# SCH_ArtNetDMX_2024-09-19.net
KiCad netlist of a schematic drawn in EasyEDA
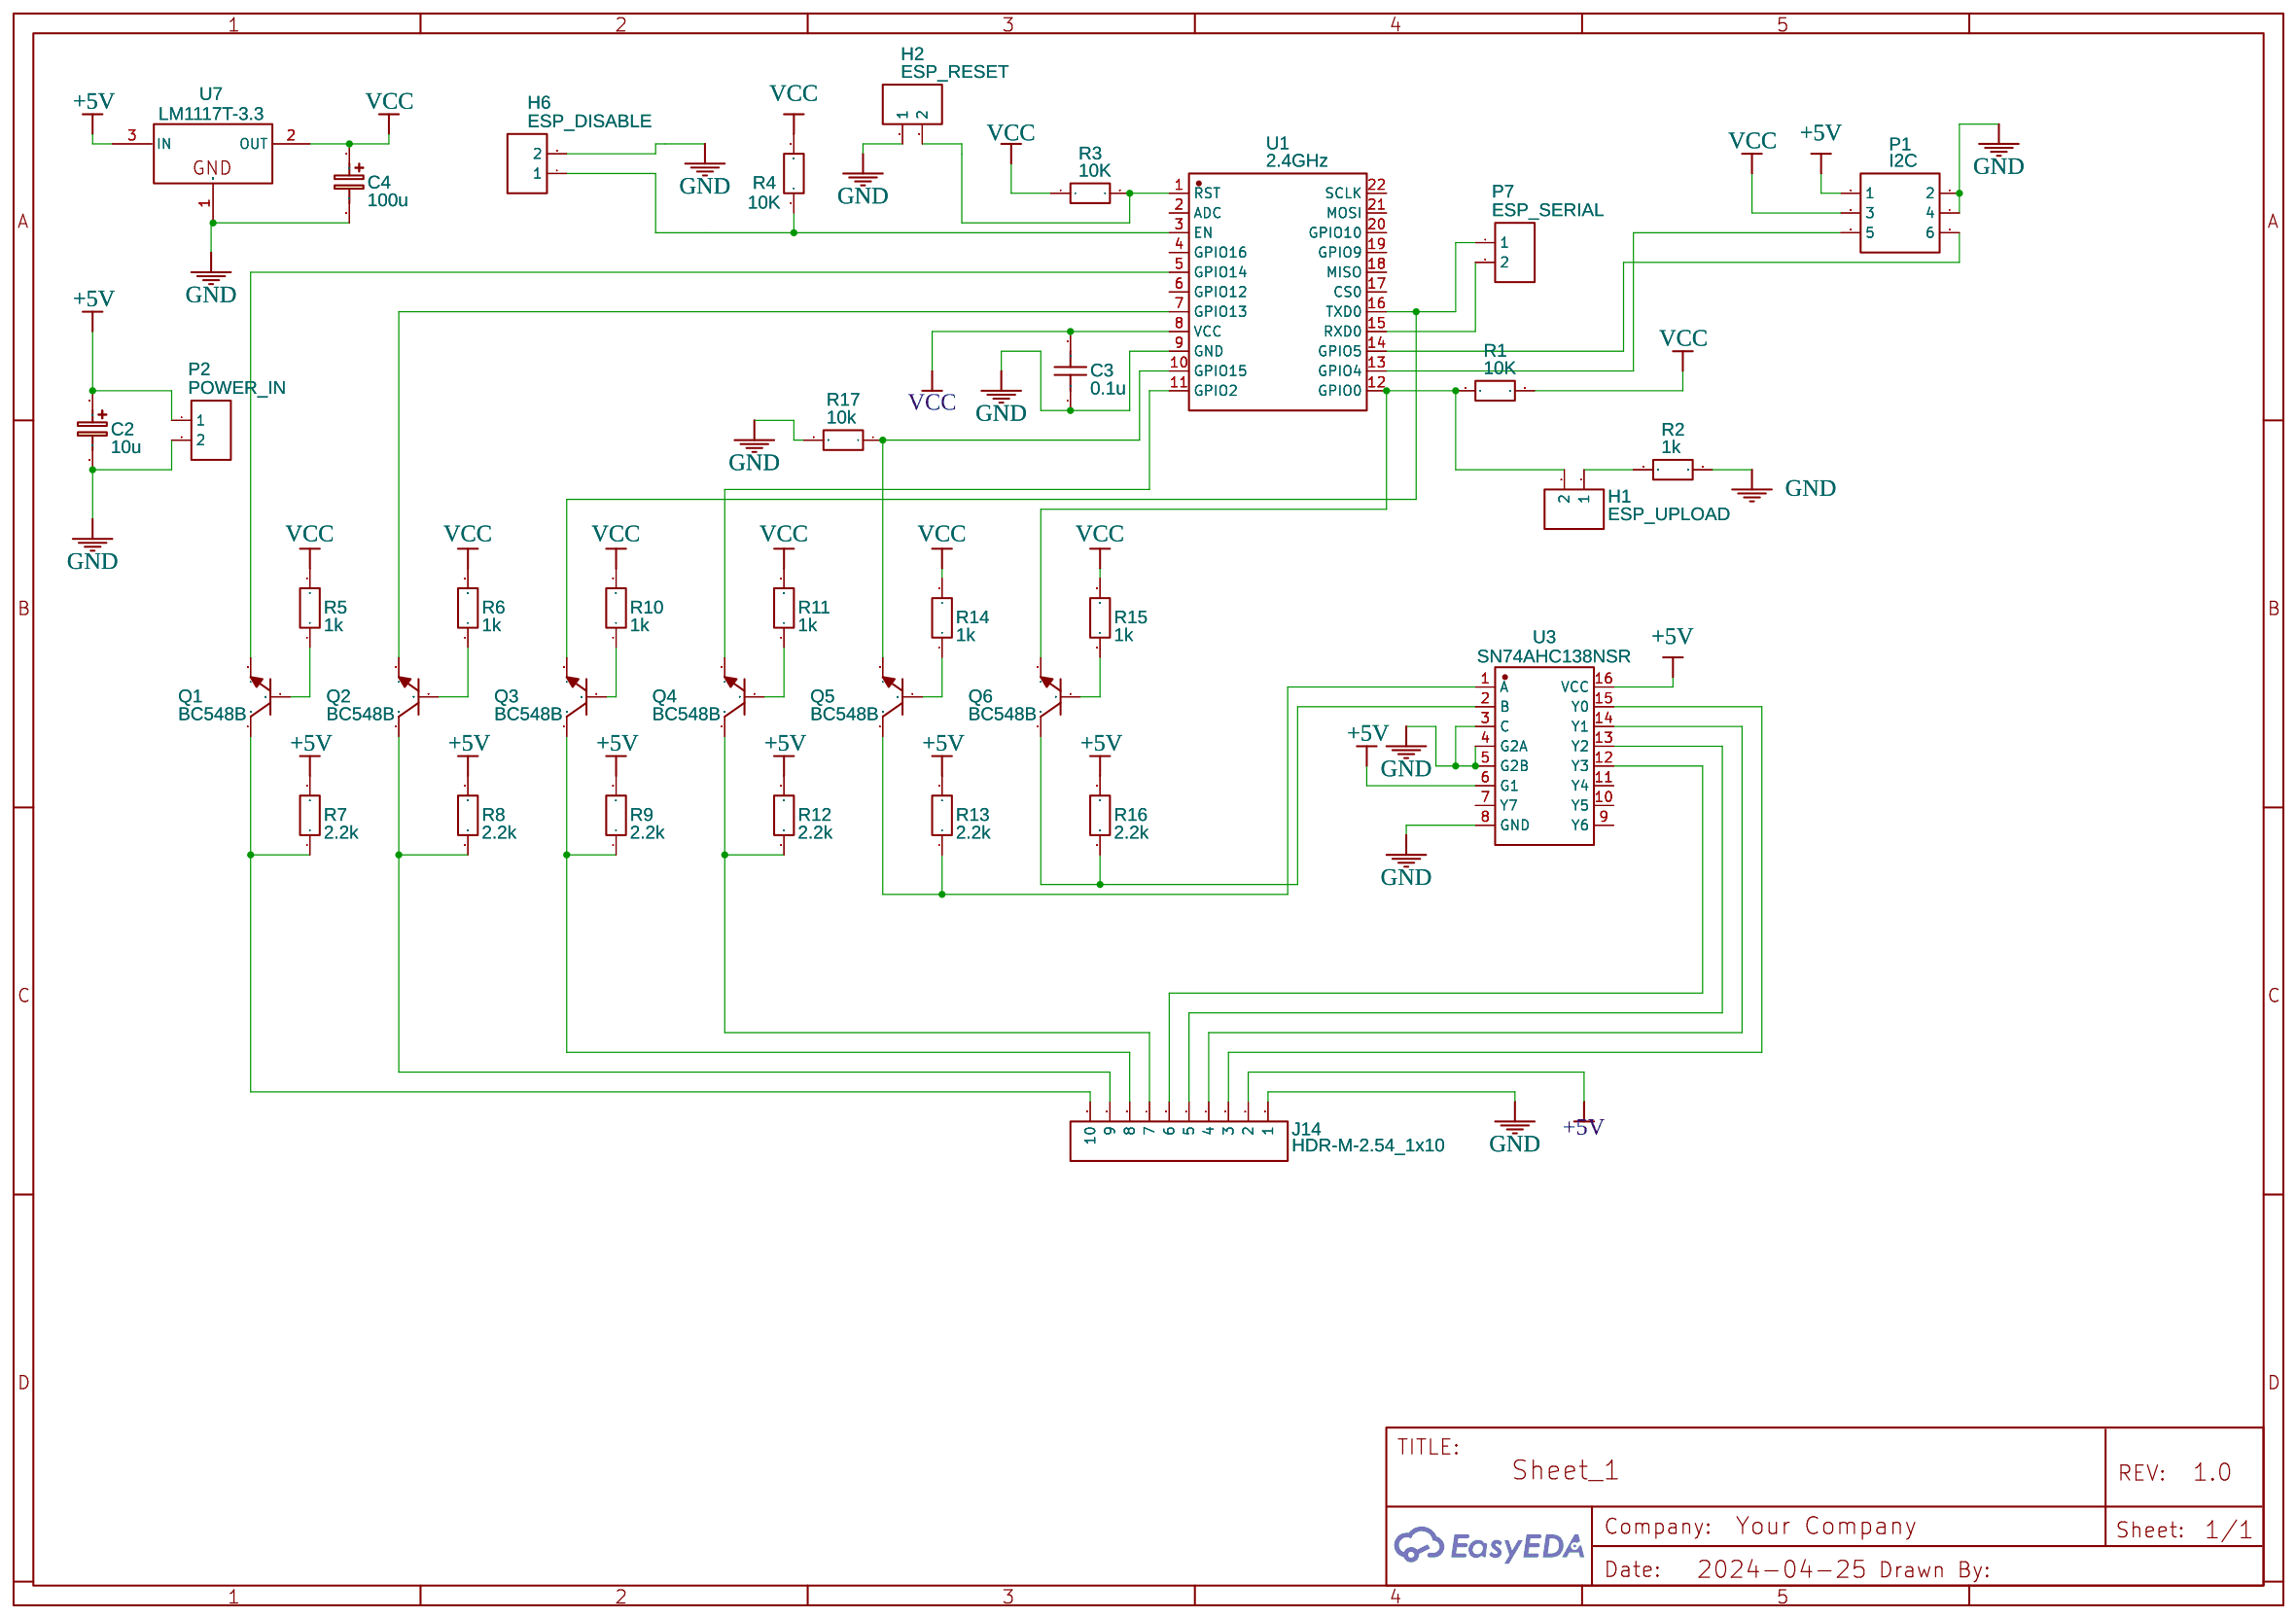
[diagram p0: Sheet_1]
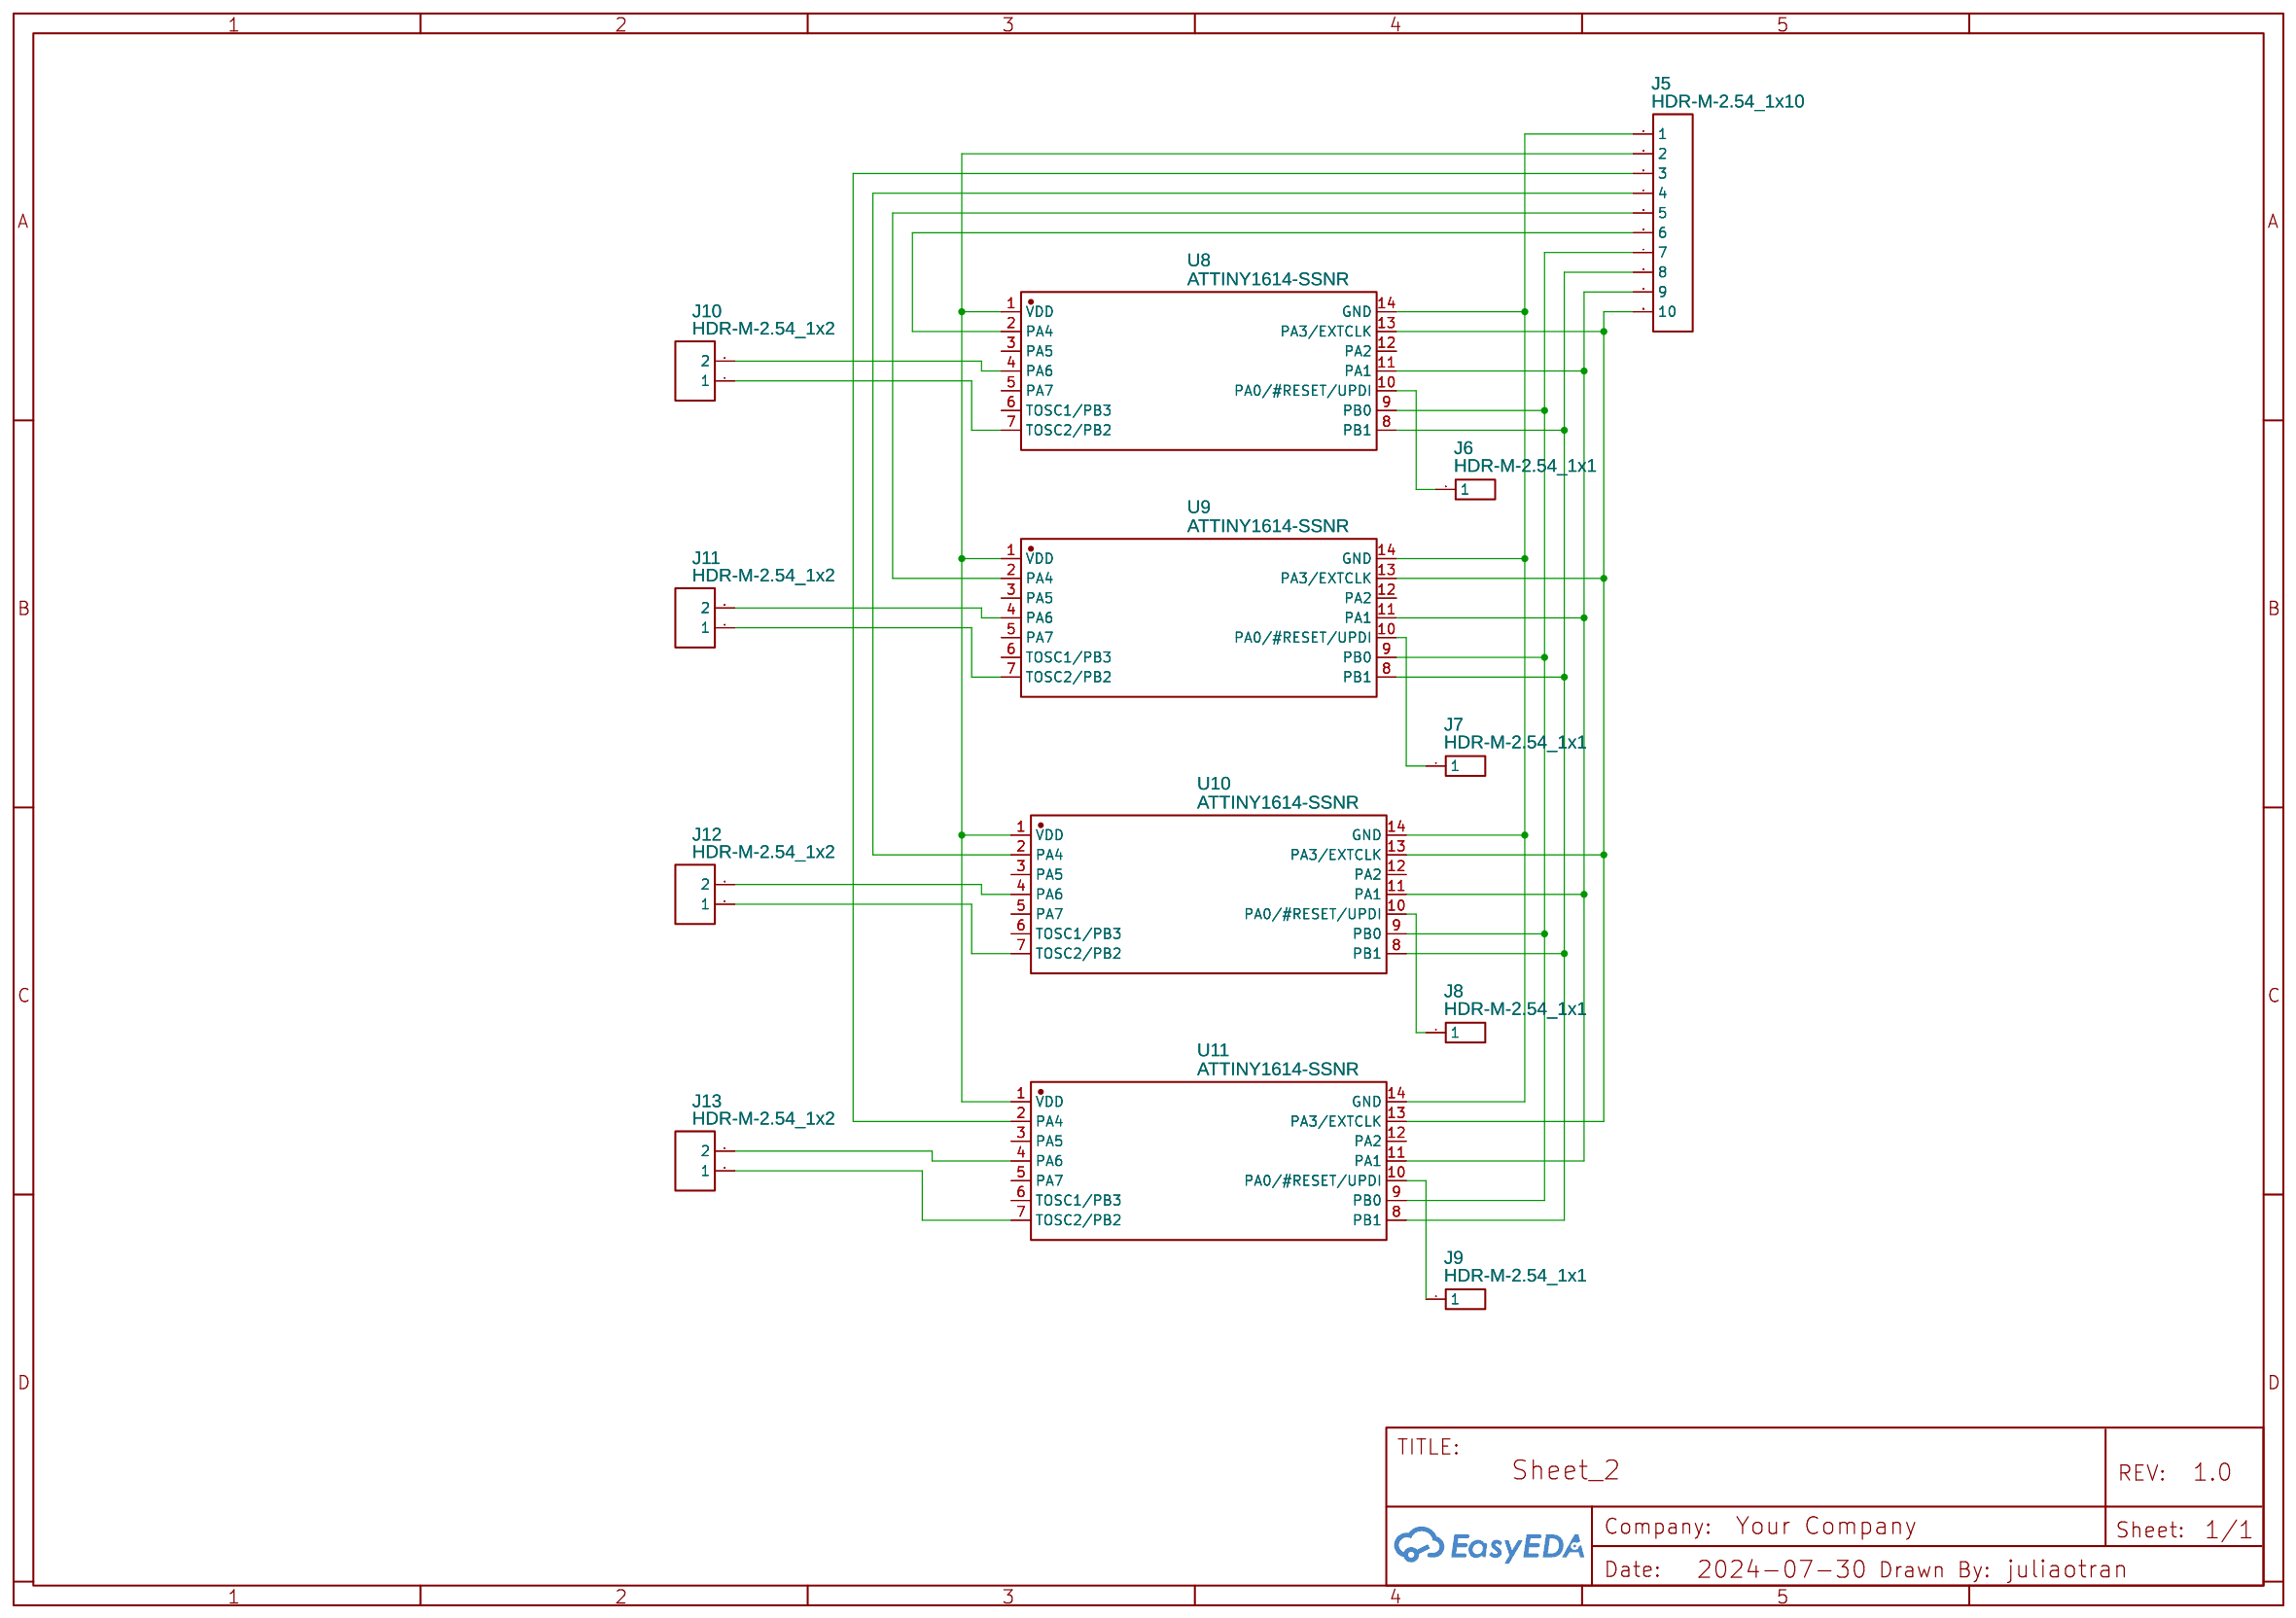
[diagram p1: Sheet_2]
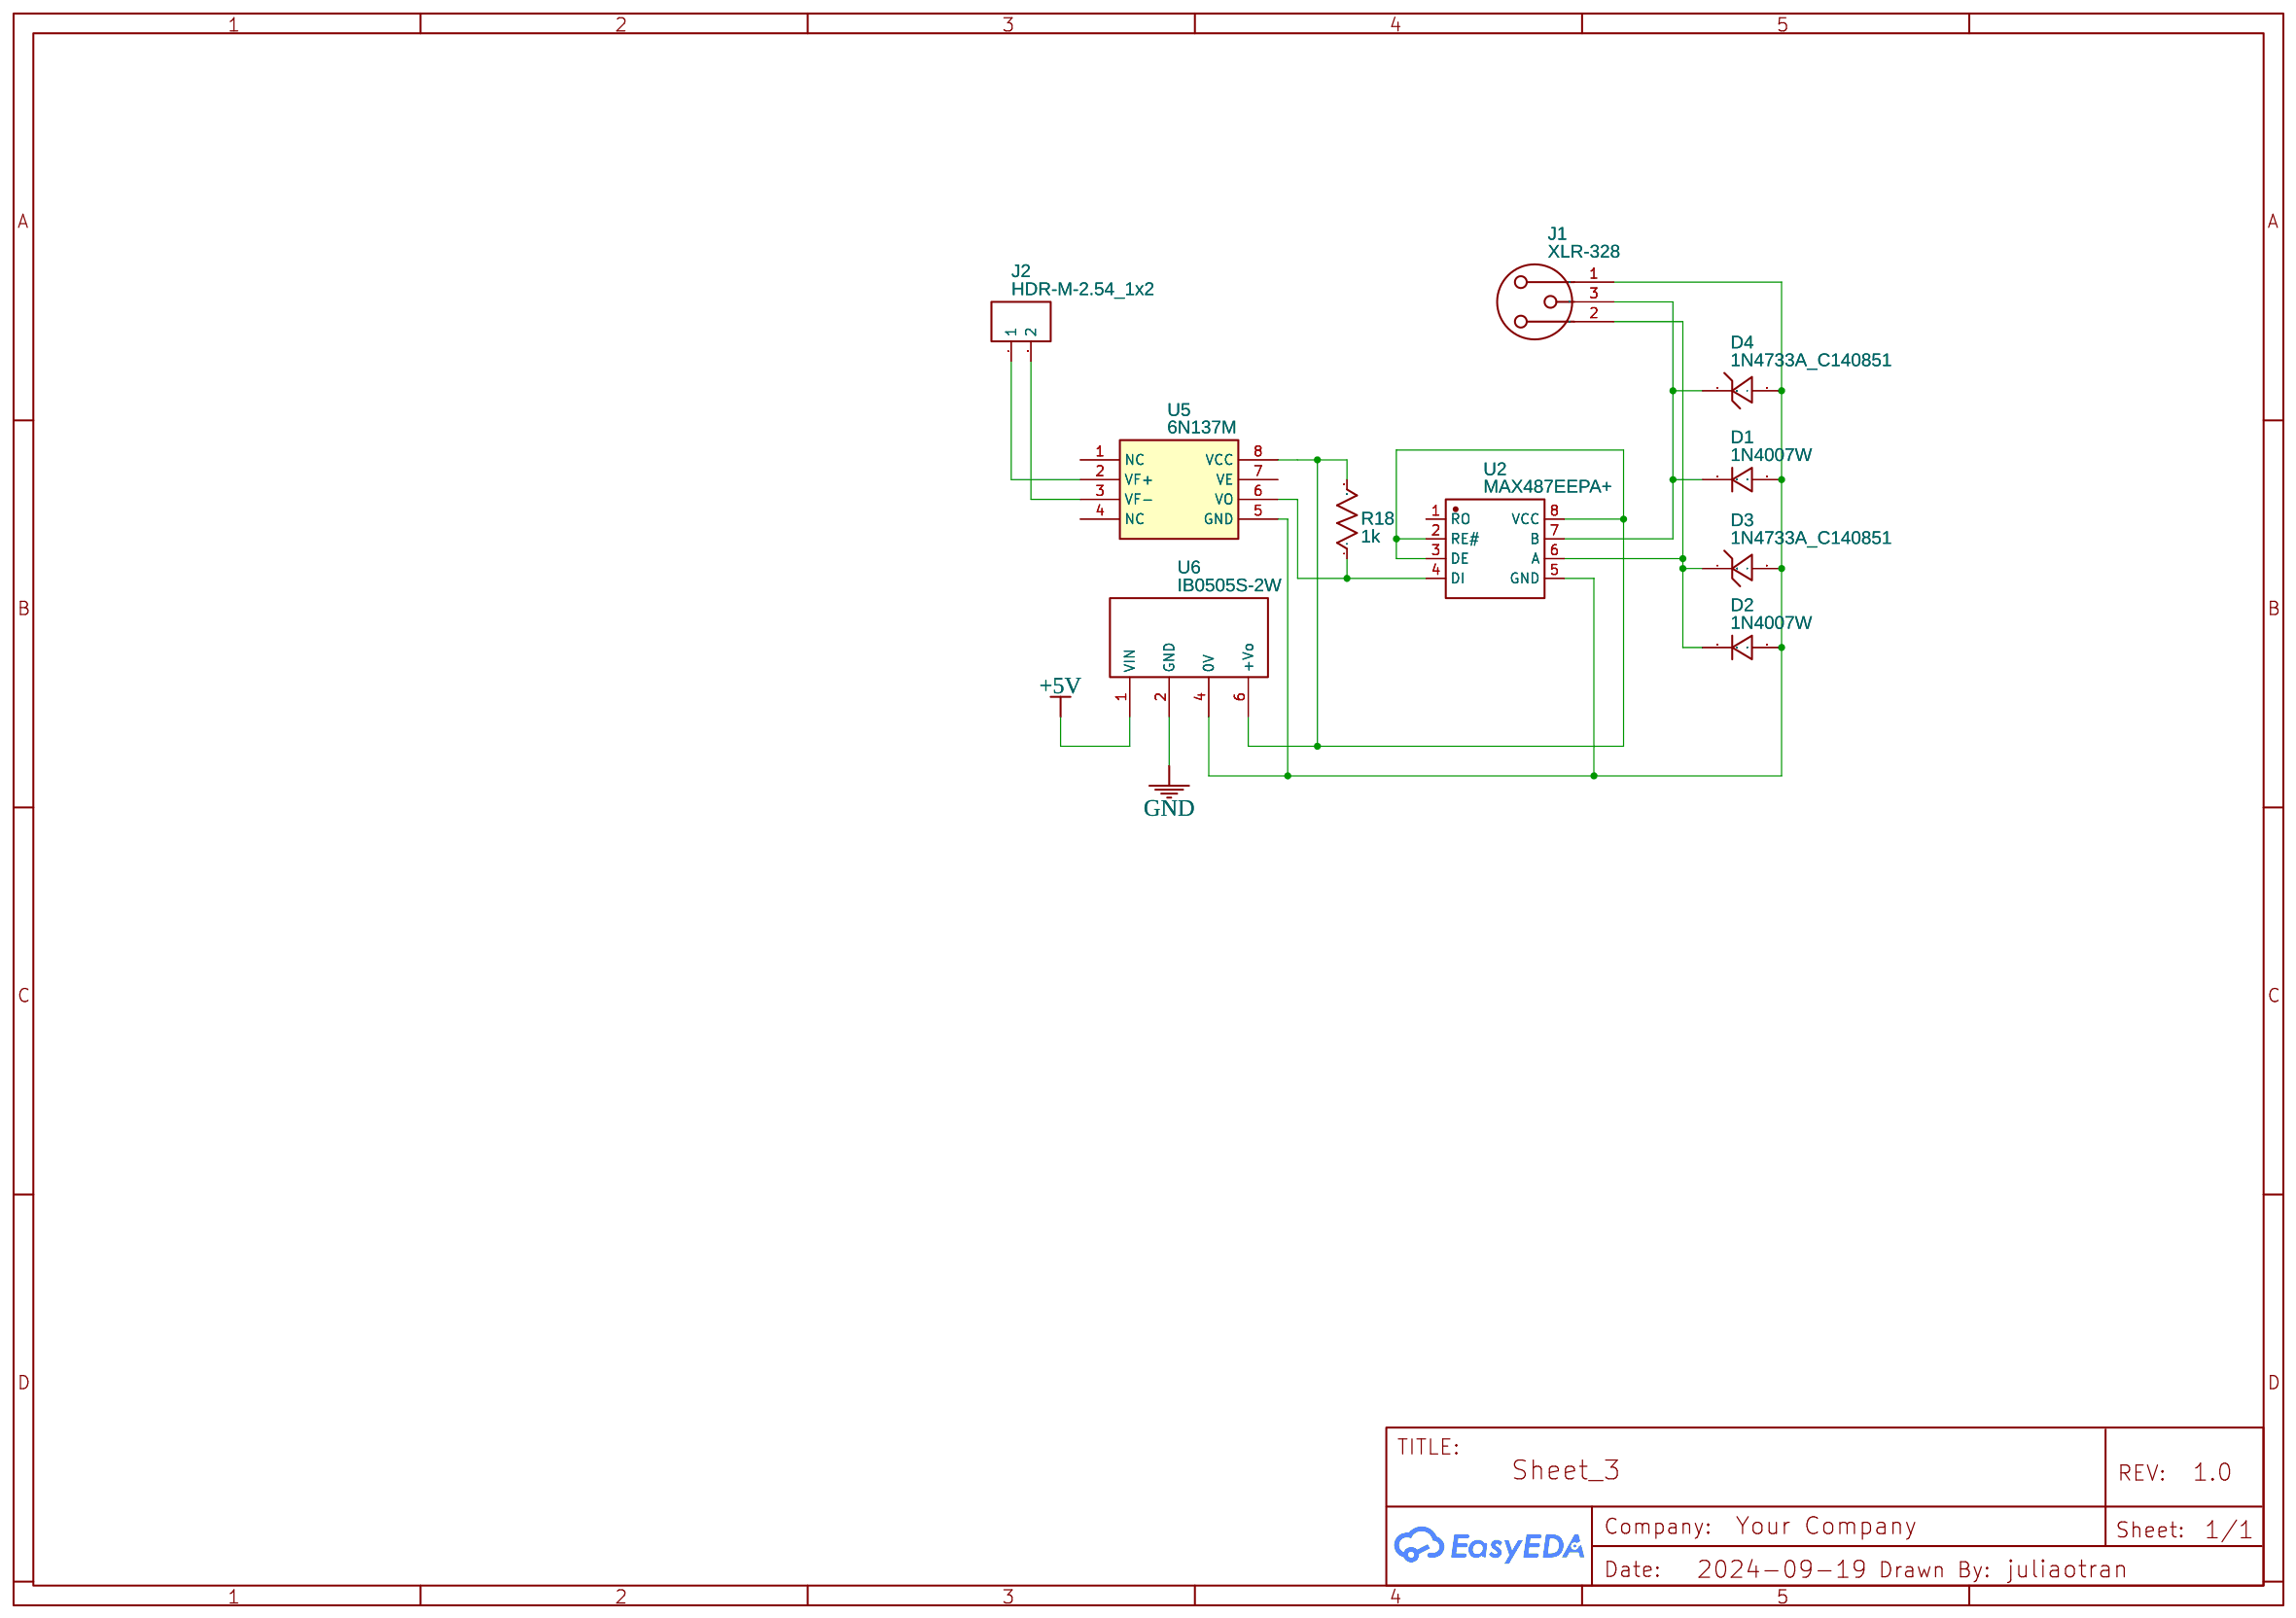
[diagram p2: Sheet_3]

(export (version "E")
  (design (tool "Eeschema 10.0.6"))
  (components
    (comp (ref "C2") (value "10u") (libsource (lib "") (part "CE_SMD_D4.0×H5.5_EU")))
    (comp (ref "C3") (value "0.1u") (libsource (lib "") (part "C_1206_US")))
    (comp (ref "C4") (value "100u") (libsource (lib "") (part "CE_TH_D5.0×F2.0_EU")))
    (comp (ref "H1") (value "ESP_UPLOAD") (libsource (lib "") (part "HDR-F-2.54_1x2")))
    (comp (ref "H2") (value "ESP_RESET") (libsource (lib "") (part "HDR-F-2.54_1x2_1")))
    (comp (ref "H6") (value "ESP_DISABLE") (libsource (lib "") (part "HDR-F-2.54_1x2_2")))
    (comp (ref "J14") (value "HDR-M-2.54_1x10") (libsource (lib "") (part "HDR-M-2.54_1x10")))
    (comp (ref "P1")
      (value "I2C")
      (fields (field (name "Manufacturer Part") "2X3 2.54mm IDC Box") (field (name "Manufacturer") "BOOMELE"))
      (libsource (lib "") (part "HDR-IDC-2.54-2X3P"))
    )
    (comp (ref "P2") (value "POWER_IN") (libsource (lib "") (part "CONN-TH_2P-P5.00")))
    (comp (ref "P7") (value "ESP_SERIAL") (libsource (lib "") (part "CONN-TH_2P-P5.00")))
    (comp (ref "Q1")
      (value "BC548B")
      (fields (field (name "Manufacturer Part") "BC548") (field (name "Manufacturer") "CJ(江苏长电/长晶)"))
      (libsource (lib "") (part "BC548B"))
    )
    (comp (ref "Q2")
      (value "BC548B")
      (fields (field (name "Manufacturer Part") "BC548") (field (name "Manufacturer") "CJ(江苏长电/长晶)"))
      (libsource (lib "") (part "BC548B"))
    )
    (comp (ref "Q3")
      (value "BC548B")
      (fields (field (name "Manufacturer Part") "BC548") (field (name "Manufacturer") "CJ(江苏长电/长晶)"))
      (libsource (lib "") (part "BC548B"))
    )
    (comp (ref "Q4")
      (value "BC548B")
      (fields (field (name "Manufacturer Part") "BC548") (field (name "Manufacturer") "CJ(江苏长电/长晶)"))
      (libsource (lib "") (part "BC548B"))
    )
    (comp (ref "Q5")
      (value "BC548B")
      (fields (field (name "Manufacturer Part") "BC548") (field (name "Manufacturer") "CJ(江苏长电/长晶)"))
      (libsource (lib "") (part "BC548B"))
    )
    (comp (ref "Q6")
      (value "BC548B")
      (fields (field (name "Manufacturer Part") "BC548") (field (name "Manufacturer") "CJ(江苏长电/长晶)"))
      (libsource (lib "") (part "BC548B"))
    )
    (comp (ref "R1") (value "10K") (libsource (lib "") (part "R_0603_EU_1")))
    (comp (ref "R2") (value "1k") (libsource (lib "") (part "R_0603_EU_1")))
    (comp (ref "R3") (value "10K") (libsource (lib "") (part "R_0603_EU_1")))
    (comp (ref "R4") (value "10K") (libsource (lib "") (part "R_0603_EU")))
    (comp (ref "R5") (value "1k") (libsource (lib "") (part "R_0603_EU")))
    (comp (ref "R6") (value "1k") (libsource (lib "") (part "R_0603_EU")))
    (comp (ref "R7") (value "2.2k") (libsource (lib "") (part "R_0603_EU")))
    (comp (ref "R8") (value "2.2k") (libsource (lib "") (part "R_0603_EU")))
    (comp (ref "R9") (value "2.2k") (libsource (lib "") (part "R_0603_EU")))
    (comp (ref "R10") (value "1k") (libsource (lib "") (part "R_0603_EU")))
    (comp (ref "R11") (value "1k") (libsource (lib "") (part "R_0603_EU")))
    (comp (ref "R12") (value "2.2k") (libsource (lib "") (part "R_0603_EU")))
    (comp (ref "R13") (value "2.2k") (libsource (lib "") (part "R_0603_EU")))
    (comp (ref "R14") (value "1k") (libsource (lib "") (part "R_0603_EU")))
    (comp (ref "R15") (value "1k") (libsource (lib "") (part "R_0603_EU")))
    (comp (ref "R16") (value "2.2k") (libsource (lib "") (part "R_0603_EU")))
    (comp (ref "R17") (value "10k") (libsource (lib "") (part "R_0603_EU_2")))
    (comp (ref "U1")
      (value "2.4GHz")
      (fields
        (field (name "Manufacturer Part") "ESP-12F(ESP8266MOD)")
        (field (name "Manufacturer") "Ai-Thinker(安信可)")
      )
      (libsource (lib "") (part "ESP-12F(ESP8266MOD)"))
    )
    (comp (ref "U3")
      (value "SN74AHC138NSR")
      (fields (field (name "Manufacturer") "TI(德州仪器)"))
      (libsource (lib "") (part "SN74AHC138NSR"))
    )
    (comp (ref "U7")
      (value "LM1117T-3.3")
      (fields (field (name "Manufacturer") "HGSEMI(华冠)"))
      (libsource (lib "") (part "LM1117T-3.3"))
    )
    (comp (ref "J5") (value "HDR-M-2.54_1x10") (libsource (lib "") (part "HDR-M-2.54_1x10")))
    (comp (ref "J6") (value "HDR-M-2.54_1x1") (libsource (lib "") (part "HDR-M-2.54_1x1")))
    (comp (ref "J7") (value "HDR-M-2.54_1x1") (libsource (lib "") (part "HDR-M-2.54_1x1")))
    (comp (ref "J8") (value "HDR-M-2.54_1x1") (libsource (lib "") (part "HDR-M-2.54_1x1")))
    (comp (ref "J9") (value "HDR-M-2.54_1x1") (libsource (lib "") (part "HDR-M-2.54_1x1")))
    (comp (ref "J10") (value "HDR-M-2.54_1x2") (libsource (lib "") (part "HDR-M-2.54_1x2")))
    (comp (ref "J11") (value "HDR-M-2.54_1x2") (libsource (lib "") (part "HDR-M-2.54_1x2")))
    (comp (ref "J12") (value "HDR-M-2.54_1x2") (libsource (lib "") (part "HDR-M-2.54_1x2")))
    (comp (ref "J13") (value "HDR-M-2.54_1x2") (libsource (lib "") (part "HDR-M-2.54_1x2")))
    (comp (ref "U8")
      (value "ATTINY1614-SSNR")
      (fields (field (name "Manufacturer") "MICROCHIP(美国微芯)"))
      (libsource (lib "") (part "ATTINY1614-SSNR"))
    )
    (comp (ref "U9")
      (value "ATTINY1614-SSNR")
      (fields (field (name "Manufacturer") "MICROCHIP(美国微芯)"))
      (libsource (lib "") (part "ATTINY1614-SSNR"))
    )
    (comp (ref "U10")
      (value "ATTINY1614-SSNR")
      (fields (field (name "Manufacturer") "MICROCHIP(美国微芯)"))
      (libsource (lib "") (part "ATTINY1614-SSNR"))
    )
    (comp (ref "U11")
      (value "ATTINY1614-SSNR")
      (fields (field (name "Manufacturer") "MICROCHIP(美国微芯)"))
      (libsource (lib "") (part "ATTINY1614-SSNR"))
    )
    (comp (ref "D1")
      (value "1N4007W")
      (fields (field (name "Manufacturer") "BLUE ROCKET"))
      (libsource (lib "") (part "1N4007W"))
    )
    (comp (ref "D2")
      (value "1N4007W")
      (fields (field (name "Manufacturer") "BLUE ROCKET"))
      (libsource (lib "") (part "1N4007W"))
    )
    (comp (ref "D3")
      (value "1N4733A_C140851")
      (fields (field (name "Manufacturer Part") "1N4733A") (field (name "Manufacturer") "onsemi(安森美)"))
      (libsource (lib "") (part "1N4733A_C140851"))
    )
    (comp (ref "D4")
      (value "1N4733A_C140851")
      (fields (field (name "Manufacturer Part") "1N4733A") (field (name "Manufacturer") "onsemi(安森美)"))
      (libsource (lib "") (part "1N4733A_C140851"))
    )
    (comp (ref "J1")
      (value "XLR-328")
      (fields (field (name "Manufacturer") "HOOYA(皓宇电子)"))
      (libsource (lib "") (part "XLR-328"))
    )
    (comp (ref "J2") (value "HDR-M-2.54_1x2") (libsource (lib "") (part "HDR-M-2.54_1x2")))
    (comp (ref "R18") (value "1k") (libsource (lib "") (part "R_0603_US")))
    (comp (ref "U2")
      (value "MAX487EEPA+")
      (fields (field (name "Manufacturer") "ADI(亚德诺)/MAXIM(美信)"))
      (libsource (lib "") (part "MAX487EEPA+"))
    )
    (comp (ref "U5")
      (value "6N137M")
      (fields (field (name "Manufacturer") "onsemi(安森美)"))
      (libsource (lib "") (part "6N137M"))
    )
    (comp (ref "U6")
      (value "IB0505S-2W")
      (fields (field (name "Manufacturer") "MORNSUN(金升阳)"))
      (libsource (lib "") (part "IB0505S-2W"))
    )
  )
  (nets
    (net (code "1") (name "+5V") (class "Default")
      (node (ref "C2") (pin "1") (pinfunction "1_1") (pintype "unspecified"))
      (node (ref "J14") (pin "2") (pinfunction "2_2") (pintype "unspecified"))
      (node (ref "P1") (pin "1") (pinfunction "1_1") (pintype "unspecified"))
      (node (ref "P2") (pin "1") (pinfunction "1_1") (pintype "unspecified"))
      (node (ref "R12") (pin "2") (pinfunction "2_2") (pintype "unspecified"))
      (node (ref "R13") (pin "2") (pinfunction "2_2") (pintype "unspecified"))
      (node (ref "R16") (pin "2") (pinfunction "2_2") (pintype "unspecified"))
      (node (ref "R7") (pin "2") (pinfunction "2_2") (pintype "unspecified"))
      (node (ref "R8") (pin "2") (pinfunction "2_2") (pintype "unspecified"))
      (node (ref "R9") (pin "2") (pinfunction "2_2") (pintype "unspecified"))
      (node (ref "U3") (pin "16") (pinfunction "VCC_16") (pintype "unspecified"))
      (node (ref "U3") (pin "6") (pinfunction "G1_6") (pintype "unspecified"))
      (node (ref "U6") (pin "1") (pinfunction "VIN_1") (pintype "unspecified"))
      (node (ref "U7") (pin "3") (pinfunction "IN_3") (pintype "unspecified"))
    )
    (net (code "2") (name "GND") (class "Default")
      (node (ref "C2") (pin "2") (pinfunction "2_2") (pintype "unspecified"))
      (node (ref "C3") (pin "1") (pinfunction "1_1") (pintype "unspecified"))
      (node (ref "C4") (pin "2") (pinfunction "2_2") (pintype "unspecified"))
      (node (ref "H2") (pin "1") (pinfunction "1_1") (pintype "input"))
      (node (ref "H6") (pin "2") (pinfunction "2_2") (pintype "input"))
      (node (ref "J14") (pin "1") (pinfunction "1_1") (pintype "unspecified"))
      (node (ref "P1") (pin "2") (pinfunction "2_2") (pintype "unspecified"))
      (node (ref "P1") (pin "4") (pinfunction "4_4") (pintype "unspecified"))
      (node (ref "P2") (pin "2") (pinfunction "2_2") (pintype "unspecified"))
      (node (ref "R17") (pin "2") (pinfunction "2_2") (pintype "unspecified"))
      (node (ref "R2") (pin "2") (pinfunction "2_2") (pintype "unspecified"))
      (node (ref "U1") (pin "9") (pinfunction "GND_9") (pintype "unspecified"))
      (node (ref "U3") (pin "3") (pinfunction "C_3") (pintype "unspecified"))
      (node (ref "U3") (pin "4") (pinfunction "G2A_4") (pintype "unspecified"))
      (node (ref "U3") (pin "5") (pinfunction "G2B_5") (pintype "unspecified"))
      (node (ref "U3") (pin "8") (pinfunction "GND_8") (pintype "unspecified"))
      (node (ref "U6") (pin "2") (pinfunction "GND_2") (pintype "unspecified"))
      (node (ref "U7") (pin "1") (pinfunction "GND_1") (pintype "unspecified"))
    )
    (net (code "3") (name "Net-(D3-A)") (class "Default")
      (node (ref "D1") (pin "2") (pinfunction "2_2") (pintype "unspecified"))
      (node (ref "D2") (pin "2") (pinfunction "2_2") (pintype "unspecified"))
      (node (ref "D3") (pin "2") (pinfunction "A_2") (pintype "unspecified"))
      (node (ref "D4") (pin "2") (pinfunction "A_2") (pintype "unspecified"))
      (node (ref "J1") (pin "1") (pinfunction "1_1") (pintype "unspecified"))
      (node (ref "U2") (pin "5") (pinfunction "GND_5") (pintype "unspecified"))
      (node (ref "U5") (pin "5") (pinfunction "GND_5") (pintype "unspecified"))
      (node (ref "U6") (pin "4") (pinfunction "0V_4") (pintype "unspecified"))
    )
    (net (code "4") (name "Net-(D3-C)") (class "Default")
      (node (ref "D2") (pin "1") (pinfunction "1_1") (pintype "unspecified"))
      (node (ref "D3") (pin "1") (pinfunction "C_1") (pintype "unspecified"))
      (node (ref "J1") (pin "2") (pinfunction "2_2") (pintype "unspecified"))
      (node (ref "U2") (pin "6") (pinfunction "A_6") (pintype "unspecified"))
    )
    (net (code "5") (name "Net-(D4-C)") (class "Default")
      (node (ref "D1") (pin "1") (pinfunction "1_1") (pintype "unspecified"))
      (node (ref "D4") (pin "1") (pinfunction "C_1") (pintype "unspecified"))
      (node (ref "J1") (pin "3") (pinfunction "3_3") (pintype "unspecified"))
      (node (ref "U2") (pin "7") (pinfunction "B_7") (pintype "unspecified"))
    )
    (net (code "6") (name "Net-(H1-Pad1)") (class "Default")
      (node (ref "H1") (pin "1") (pinfunction "1_1") (pintype "input"))
      (node (ref "R2") (pin "1") (pinfunction "1_1") (pintype "unspecified"))
    )
    (net (code "7") (name "Net-(Q1-B)") (class "Default")
      (node (ref "Q1") (pin "2") (pinfunction "B_2") (pintype "unspecified"))
      (node (ref "R5") (pin "1") (pinfunction "1_1") (pintype "unspecified"))
    )
    (net (code "8") (name "Net-(Q1-C)") (class "Default")
      (node (ref "J14") (pin "10") (pinfunction "10_10") (pintype "unspecified"))
      (node (ref "Q1") (pin "1") (pinfunction "C_1") (pintype "unspecified"))
      (node (ref "R7") (pin "1") (pinfunction "1_1") (pintype "unspecified"))
    )
    (net (code "9") (name "Net-(Q1-E)") (class "Default")
      (node (ref "Q1") (pin "3") (pinfunction "E_3") (pintype "unspecified"))
      (node (ref "U1") (pin "5") (pinfunction "GPIO14_5") (pintype "unspecified"))
    )
    (net (code "10") (name "Net-(Q2-B)") (class "Default")
      (node (ref "Q2") (pin "2") (pinfunction "B_2") (pintype "unspecified"))
      (node (ref "R6") (pin "1") (pinfunction "1_1") (pintype "unspecified"))
    )
    (net (code "11") (name "Net-(Q2-C)") (class "Default")
      (node (ref "J14") (pin "9") (pinfunction "9_9") (pintype "unspecified"))
      (node (ref "Q2") (pin "1") (pinfunction "C_1") (pintype "unspecified"))
      (node (ref "R8") (pin "1") (pinfunction "1_1") (pintype "unspecified"))
    )
    (net (code "12") (name "Net-(Q2-E)") (class "Default")
      (node (ref "Q2") (pin "3") (pinfunction "E_3") (pintype "unspecified"))
      (node (ref "U1") (pin "7") (pinfunction "GPIO13_7") (pintype "unspecified"))
    )
    (net (code "13") (name "Net-(Q3-B)") (class "Default")
      (node (ref "Q3") (pin "2") (pinfunction "B_2") (pintype "unspecified"))
      (node (ref "R10") (pin "1") (pinfunction "1_1") (pintype "unspecified"))
    )
    (net (code "14") (name "Net-(Q3-C)") (class "Default")
      (node (ref "J14") (pin "8") (pinfunction "8_8") (pintype "unspecified"))
      (node (ref "Q3") (pin "1") (pinfunction "C_1") (pintype "unspecified"))
      (node (ref "R9") (pin "1") (pinfunction "1_1") (pintype "unspecified"))
    )
    (net (code "15") (name "Net-(Q3-E)") (class "Default")
      (node (ref "P7") (pin "1") (pinfunction "1_1") (pintype "unspecified"))
      (node (ref "Q3") (pin "3") (pinfunction "E_3") (pintype "unspecified"))
      (node (ref "U1") (pin "16") (pinfunction "TXD0_16") (pintype "unspecified"))
    )
    (net (code "16") (name "Net-(Q4-B)") (class "Default")
      (node (ref "Q4") (pin "2") (pinfunction "B_2") (pintype "unspecified"))
      (node (ref "R11") (pin "1") (pinfunction "1_1") (pintype "unspecified"))
    )
    (net (code "17") (name "Net-(Q4-C)") (class "Default")
      (node (ref "J14") (pin "7") (pinfunction "7_7") (pintype "unspecified"))
      (node (ref "Q4") (pin "1") (pinfunction "C_1") (pintype "unspecified"))
      (node (ref "R12") (pin "1") (pinfunction "1_1") (pintype "unspecified"))
    )
    (net (code "18") (name "Net-(Q4-E)") (class "Default")
      (node (ref "Q4") (pin "3") (pinfunction "E_3") (pintype "unspecified"))
      (node (ref "U1") (pin "11") (pinfunction "GPIO2_11") (pintype "unspecified"))
    )
    (net (code "19") (name "Net-(Q5-B)") (class "Default")
      (node (ref "Q5") (pin "2") (pinfunction "B_2") (pintype "unspecified"))
      (node (ref "R14") (pin "1") (pinfunction "1_1") (pintype "unspecified"))
    )
    (net (code "20") (name "Net-(Q5-C)") (class "Default")
      (node (ref "Q5") (pin "1") (pinfunction "C_1") (pintype "unspecified"))
      (node (ref "R13") (pin "1") (pinfunction "1_1") (pintype "unspecified"))
      (node (ref "U3") (pin "1") (pinfunction "A_1") (pintype "unspecified"))
    )
    (net (code "21") (name "Net-(Q5-E)") (class "Default")
      (node (ref "Q5") (pin "3") (pinfunction "E_3") (pintype "unspecified"))
      (node (ref "R17") (pin "1") (pinfunction "1_1") (pintype "unspecified"))
      (node (ref "U1") (pin "10") (pinfunction "GPIO15_10") (pintype "unspecified"))
    )
    (net (code "22") (name "Net-(Q6-B)") (class "Default")
      (node (ref "Q6") (pin "2") (pinfunction "B_2") (pintype "unspecified"))
      (node (ref "R15") (pin "1") (pinfunction "1_1") (pintype "unspecified"))
    )
    (net (code "23") (name "Net-(Q6-C)") (class "Default")
      (node (ref "Q6") (pin "1") (pinfunction "C_1") (pintype "unspecified"))
      (node (ref "R16") (pin "1") (pinfunction "1_1") (pintype "unspecified"))
      (node (ref "U3") (pin "2") (pinfunction "B_2") (pintype "unspecified"))
    )
    (net (code "24") (name "Net-(Q6-E)") (class "Default")
      (node (ref "H1") (pin "2") (pinfunction "2_2") (pintype "input"))
      (node (ref "Q6") (pin "3") (pinfunction "E_3") (pintype "unspecified"))
      (node (ref "R1") (pin "1") (pinfunction "1_1") (pintype "unspecified"))
      (node (ref "U1") (pin "12") (pinfunction "GPIO0_12") (pintype "unspecified"))
    )
    (net (code "25") (name "Net-(U1-EN)") (class "Default")
      (node (ref "H6") (pin "1") (pinfunction "1_1") (pintype "input"))
      (node (ref "R4") (pin "1") (pinfunction "1_1") (pintype "unspecified"))
      (node (ref "U1") (pin "3") (pinfunction "EN_3") (pintype "unspecified"))
    )
    (net (code "26") (name "Net-(U1-GPIO4)") (class "Default")
      (node (ref "P1") (pin "5") (pinfunction "5_5") (pintype "unspecified"))
      (node (ref "U1") (pin "13") (pinfunction "GPIO4_13") (pintype "unspecified"))
    )
    (net (code "27") (name "Net-(U1-GPIO5)") (class "Default")
      (node (ref "P1") (pin "6") (pinfunction "6_6") (pintype "unspecified"))
      (node (ref "U1") (pin "14") (pinfunction "GPIO5_14") (pintype "unspecified"))
    )
    (net (code "28") (name "Net-(U1-RST)") (class "Default")
      (node (ref "H2") (pin "2") (pinfunction "2_2") (pintype "input"))
      (node (ref "R3") (pin "2") (pinfunction "2_2") (pintype "unspecified"))
      (node (ref "U1") (pin "1") (pinfunction "RST_1") (pintype "unspecified"))
    )
    (net (code "29") (name "Net-(U1-RXD0)") (class "Default")
      (node (ref "P7") (pin "2") (pinfunction "2_2") (pintype "unspecified"))
      (node (ref "U1") (pin "15") (pinfunction "RXD0_15") (pintype "unspecified"))
    )
    (net (code "30") (name "Net-(U2-DE)") (class "Default")
      (node (ref "R18") (pin "2") (pinfunction "2_2") (pintype "unspecified"))
      (node (ref "U2") (pin "2") (pinfunction "RE#_2") (pintype "unspecified"))
      (node (ref "U2") (pin "3") (pinfunction "DE_3") (pintype "unspecified"))
      (node (ref "U2") (pin "8") (pinfunction "VCC_8") (pintype "unspecified"))
      (node (ref "U5") (pin "8") (pinfunction "VCC_8") (pintype "unspecified"))
      (node (ref "U6") (pin "6") (pinfunction "+Vo_6") (pintype "unspecified"))
    )
    (net (code "31") (name "Net-(U2-DI)") (class "Default")
      (node (ref "R18") (pin "1") (pinfunction "1_1") (pintype "unspecified"))
      (node (ref "U2") (pin "4") (pinfunction "DI_4") (pintype "unspecified"))
      (node (ref "U5") (pin "6") (pinfunction "VO_6") (pintype "unspecified"))
    )
    (net (code "32") (name "Net-(U3-Y0)") (class "Default")
      (node (ref "J14") (pin "3") (pinfunction "3_3") (pintype "unspecified"))
      (node (ref "U3") (pin "15") (pinfunction "Y0_15") (pintype "unspecified"))
    )
    (net (code "33") (name "Net-(U3-Y1)") (class "Default")
      (node (ref "J14") (pin "4") (pinfunction "4_4") (pintype "unspecified"))
      (node (ref "U3") (pin "14") (pinfunction "Y1_14") (pintype "unspecified"))
    )
    (net (code "34") (name "Net-(U3-Y2)") (class "Default")
      (node (ref "J14") (pin "5") (pinfunction "5_5") (pintype "unspecified"))
      (node (ref "U3") (pin "13") (pinfunction "Y2_13") (pintype "unspecified"))
    )
    (net (code "35") (name "Net-(U3-Y3)") (class "Default")
      (node (ref "J14") (pin "6") (pinfunction "6_6") (pintype "unspecified"))
      (node (ref "U3") (pin "12") (pinfunction "Y3_12") (pintype "unspecified"))
    )
    (net (code "36") (name "Net-(U5-VF+)") (class "Default")
      (node (ref "J2") (pin "1") (pinfunction "1_1") (pintype "unspecified"))
      (node (ref "U5") (pin "2") (pinfunction "VF+_2") (pintype "unspecified"))
    )
    (net (code "37") (name "Net-(U5-VF-)") (class "Default")
      (node (ref "J2") (pin "2") (pinfunction "2_2") (pintype "unspecified"))
      (node (ref "U5") (pin "3") (pinfunction "VF-_3") (pintype "unspecified"))
    )
    (net (code "38") (name "Net-(U8-PA0{slash}#RESET{slash}UPDI)") (class "Default")
      (node (ref "J6") (pin "1") (pinfunction "1_1") (pintype "input"))
      (node (ref "U8") (pin "10") (pinfunction "PA0/#RESET/UPDI_10") (pintype "unspecified"))
    )
    (net (code "39") (name "Net-(U8-PA4)") (class "Default")
      (node (ref "J5") (pin "6") (pinfunction "6_6") (pintype "unspecified"))
      (node (ref "U8") (pin "2") (pinfunction "PA4_2") (pintype "unspecified"))
    )
    (net (code "40") (name "Net-(U8-PA6)") (class "Default")
      (node (ref "J10") (pin "2") (pinfunction "2_2") (pintype "unspecified"))
      (node (ref "U8") (pin "4") (pinfunction "PA6_4") (pintype "unspecified"))
    )
    (net (code "41") (name "Net-(U8-TOSC2{slash}PB2)") (class "Default")
      (node (ref "J10") (pin "1") (pinfunction "1_1") (pintype "unspecified"))
      (node (ref "U8") (pin "7") (pinfunction "TOSC2/PB2_7") (pintype "unspecified"))
    )
    (net (code "42") (name "Net-(U9-PA0{slash}#RESET{slash}UPDI)") (class "Default")
      (node (ref "J7") (pin "1") (pinfunction "1_1") (pintype "input"))
      (node (ref "U9") (pin "10") (pinfunction "PA0/#RESET/UPDI_10") (pintype "unspecified"))
    )
    (net (code "43") (name "Net-(U9-PA4)") (class "Default")
      (node (ref "J5") (pin "5") (pinfunction "5_5") (pintype "unspecified"))
      (node (ref "U9") (pin "2") (pinfunction "PA4_2") (pintype "unspecified"))
    )
    (net (code "44") (name "Net-(U9-PA6)") (class "Default")
      (node (ref "J11") (pin "2") (pinfunction "2_2") (pintype "unspecified"))
      (node (ref "U9") (pin "4") (pinfunction "PA6_4") (pintype "unspecified"))
    )
    (net (code "45") (name "Net-(U9-TOSC2{slash}PB2)") (class "Default")
      (node (ref "J11") (pin "1") (pinfunction "1_1") (pintype "unspecified"))
      (node (ref "U9") (pin "7") (pinfunction "TOSC2/PB2_7") (pintype "unspecified"))
    )
    (net (code "46") (name "Net-(U10-GND)") (class "Default")
      (node (ref "J5") (pin "1") (pinfunction "1_1") (pintype "unspecified"))
      (node (ref "U10") (pin "14") (pinfunction "GND_14") (pintype "unspecified"))
      (node (ref "U11") (pin "14") (pinfunction "GND_14") (pintype "unspecified"))
      (node (ref "U8") (pin "14") (pinfunction "GND_14") (pintype "unspecified"))
      (node (ref "U9") (pin "14") (pinfunction "GND_14") (pintype "unspecified"))
    )
    (net (code "47") (name "Net-(U10-PA0{slash}#RESET{slash}UPDI)") (class "Default")
      (node (ref "J8") (pin "1") (pinfunction "1_1") (pintype "input"))
      (node (ref "U10") (pin "10") (pinfunction "PA0/#RESET/UPDI_10") (pintype "unspecified"))
    )
    (net (code "48") (name "Net-(U10-PA1)") (class "Default")
      (node (ref "J5") (pin "9") (pinfunction "9_9") (pintype "unspecified"))
      (node (ref "U10") (pin "11") (pinfunction "PA1_11") (pintype "unspecified"))
      (node (ref "U11") (pin "11") (pinfunction "PA1_11") (pintype "unspecified"))
      (node (ref "U8") (pin "11") (pinfunction "PA1_11") (pintype "unspecified"))
      (node (ref "U9") (pin "11") (pinfunction "PA1_11") (pintype "unspecified"))
    )
    (net (code "49") (name "Net-(U10-PA3{slash}EXTCLK)") (class "Default")
      (node (ref "J5") (pin "10") (pinfunction "10_10") (pintype "unspecified"))
      (node (ref "U10") (pin "13") (pinfunction "PA3/EXTCLK_13") (pintype "unspecified"))
      (node (ref "U11") (pin "13") (pinfunction "PA3/EXTCLK_13") (pintype "unspecified"))
      (node (ref "U8") (pin "13") (pinfunction "PA3/EXTCLK_13") (pintype "unspecified"))
      (node (ref "U9") (pin "13") (pinfunction "PA3/EXTCLK_13") (pintype "unspecified"))
    )
    (net (code "50") (name "Net-(U10-PA4)") (class "Default")
      (node (ref "J5") (pin "4") (pinfunction "4_4") (pintype "unspecified"))
      (node (ref "U10") (pin "2") (pinfunction "PA4_2") (pintype "unspecified"))
    )
    (net (code "51") (name "Net-(U10-PA6)") (class "Default")
      (node (ref "J12") (pin "2") (pinfunction "2_2") (pintype "unspecified"))
      (node (ref "U10") (pin "4") (pinfunction "PA6_4") (pintype "unspecified"))
    )
    (net (code "52") (name "Net-(U10-PB0)") (class "Default")
      (node (ref "J5") (pin "7") (pinfunction "7_7") (pintype "unspecified"))
      (node (ref "U10") (pin "9") (pinfunction "PB0_9") (pintype "unspecified"))
      (node (ref "U11") (pin "9") (pinfunction "PB0_9") (pintype "unspecified"))
      (node (ref "U8") (pin "9") (pinfunction "PB0_9") (pintype "unspecified"))
      (node (ref "U9") (pin "9") (pinfunction "PB0_9") (pintype "unspecified"))
    )
    (net (code "53") (name "Net-(U10-PB1)") (class "Default")
      (node (ref "J5") (pin "8") (pinfunction "8_8") (pintype "unspecified"))
      (node (ref "U10") (pin "8") (pinfunction "PB1_8") (pintype "unspecified"))
      (node (ref "U11") (pin "8") (pinfunction "PB1_8") (pintype "unspecified"))
      (node (ref "U8") (pin "8") (pinfunction "PB1_8") (pintype "unspecified"))
      (node (ref "U9") (pin "8") (pinfunction "PB1_8") (pintype "unspecified"))
    )
    (net (code "54") (name "Net-(U10-TOSC2{slash}PB2)") (class "Default")
      (node (ref "J12") (pin "1") (pinfunction "1_1") (pintype "unspecified"))
      (node (ref "U10") (pin "7") (pinfunction "TOSC2/PB2_7") (pintype "unspecified"))
    )
    (net (code "55") (name "Net-(U10-VDD)") (class "Default")
      (node (ref "J5") (pin "2") (pinfunction "2_2") (pintype "unspecified"))
      (node (ref "U10") (pin "1") (pinfunction "VDD_1") (pintype "unspecified"))
      (node (ref "U11") (pin "1") (pinfunction "VDD_1") (pintype "unspecified"))
      (node (ref "U8") (pin "1") (pinfunction "VDD_1") (pintype "unspecified"))
      (node (ref "U9") (pin "1") (pinfunction "VDD_1") (pintype "unspecified"))
    )
    (net (code "56") (name "Net-(U11-PA0{slash}#RESET{slash}UPDI)") (class "Default")
      (node (ref "J9") (pin "1") (pinfunction "1_1") (pintype "input"))
      (node (ref "U11") (pin "10") (pinfunction "PA0/#RESET/UPDI_10") (pintype "unspecified"))
    )
    (net (code "57") (name "Net-(U11-PA4)") (class "Default")
      (node (ref "J5") (pin "3") (pinfunction "3_3") (pintype "unspecified"))
      (node (ref "U11") (pin "2") (pinfunction "PA4_2") (pintype "unspecified"))
    )
    (net (code "58") (name "Net-(U11-PA6)") (class "Default")
      (node (ref "J13") (pin "2") (pinfunction "2_2") (pintype "unspecified"))
      (node (ref "U11") (pin "4") (pinfunction "PA6_4") (pintype "unspecified"))
    )
    (net (code "59") (name "Net-(U11-TOSC2{slash}PB2)") (class "Default")
      (node (ref "J13") (pin "1") (pinfunction "1_1") (pintype "unspecified"))
      (node (ref "U11") (pin "7") (pinfunction "TOSC2/PB2_7") (pintype "unspecified"))
    )
    (net (code "60") (name "VCC") (class "Default")
      (node (ref "C3") (pin "2") (pinfunction "2_2") (pintype "unspecified"))
      (node (ref "C4") (pin "1") (pinfunction "1_1") (pintype "unspecified"))
      (node (ref "P1") (pin "3") (pinfunction "3_3") (pintype "unspecified"))
      (node (ref "R1") (pin "2") (pinfunction "2_2") (pintype "unspecified"))
      (node (ref "R10") (pin "2") (pinfunction "2_2") (pintype "unspecified"))
      (node (ref "R11") (pin "2") (pinfunction "2_2") (pintype "unspecified"))
      (node (ref "R14") (pin "2") (pinfunction "2_2") (pintype "unspecified"))
      (node (ref "R15") (pin "2") (pinfunction "2_2") (pintype "unspecified"))
      (node (ref "R3") (pin "1") (pinfunction "1_1") (pintype "unspecified"))
      (node (ref "R4") (pin "2") (pinfunction "2_2") (pintype "unspecified"))
      (node (ref "R5") (pin "2") (pinfunction "2_2") (pintype "unspecified"))
      (node (ref "R6") (pin "2") (pinfunction "2_2") (pintype "unspecified"))
      (node (ref "U1") (pin "8") (pinfunction "VCC_8") (pintype "unspecified"))
      (node (ref "U7") (pin "2") (pinfunction "OUT_2") (pintype "unspecified"))
    )
    (net (code "61") (name "unconnected-(U1-ADC-Pad2)") (class "Default")
      (node (ref "U1") (pin "2") (pinfunction "ADC_2") (pintype "unspecified"))
    )
    (net (code "62") (name "unconnected-(U1-CS0-Pad17)") (class "Default")
      (node (ref "U1") (pin "17") (pinfunction "CS0_17") (pintype "unspecified"))
    )
    (net (code "63") (name "unconnected-(U1-GPIO9-Pad19)") (class "Default")
      (node (ref "U1") (pin "19") (pinfunction "GPIO9_19") (pintype "unspecified"))
    )
    (net (code "64") (name "unconnected-(U1-GPIO10-Pad20)") (class "Default")
      (node (ref "U1") (pin "20") (pinfunction "GPIO10_20") (pintype "unspecified"))
    )
    (net (code "65") (name "unconnected-(U1-GPIO12-Pad6)") (class "Default")
      (node (ref "U1") (pin "6") (pinfunction "GPIO12_6") (pintype "unspecified"))
    )
    (net (code "66") (name "unconnected-(U1-GPIO16-Pad4)") (class "Default")
      (node (ref "U1") (pin "4") (pinfunction "GPIO16_4") (pintype "unspecified"))
    )
    (net (code "67") (name "unconnected-(U1-MISO-Pad18)") (class "Default")
      (node (ref "U1") (pin "18") (pinfunction "MISO_18") (pintype "unspecified"))
    )
    (net (code "68") (name "unconnected-(U1-MOSI-Pad21)") (class "Default")
      (node (ref "U1") (pin "21") (pinfunction "MOSI_21") (pintype "unspecified"))
    )
    (net (code "69") (name "unconnected-(U1-SCLK-Pad22)") (class "Default")
      (node (ref "U1") (pin "22") (pinfunction "SCLK_22") (pintype "unspecified"))
    )
    (net (code "70") (name "unconnected-(U2-RO-Pad1)") (class "Default")
      (node (ref "U2") (pin "1") (pinfunction "RO_1") (pintype "unspecified"))
    )
    (net (code "71") (name "unconnected-(U3-Y4-Pad11)") (class "Default")
      (node (ref "U3") (pin "11") (pinfunction "Y4_11") (pintype "unspecified"))
    )
    (net (code "72") (name "unconnected-(U3-Y5-Pad10)") (class "Default")
      (node (ref "U3") (pin "10") (pinfunction "Y5_10") (pintype "unspecified"))
    )
    (net (code "73") (name "unconnected-(U3-Y6-Pad9)") (class "Default")
      (node (ref "U3") (pin "9") (pinfunction "Y6_9") (pintype "unspecified"))
    )
    (net (code "74") (name "unconnected-(U3-Y7-Pad7)") (class "Default")
      (node (ref "U3") (pin "7") (pinfunction "Y7_7") (pintype "unspecified"))
    )
    (net (code "75") (name "unconnected-(U5-NC-Pad1)") (class "Default")
      (node (ref "U5") (pin "1") (pinfunction "NC_1") (pintype "unspecified"))
    )
    (net (code "76") (name "unconnected-(U5-NC-Pad4)") (class "Default")
      (node (ref "U5") (pin "4") (pinfunction "NC_4") (pintype "unspecified"))
    )
    (net (code "77") (name "unconnected-(U5-VE-Pad7)") (class "Default")
      (node (ref "U5") (pin "7") (pinfunction "VE_7") (pintype "unspecified"))
    )
    (net (code "78") (name "unconnected-(U8-PA2-Pad12)") (class "Default")
      (node (ref "U8") (pin "12") (pinfunction "PA2_12") (pintype "unspecified"))
    )
    (net (code "79") (name "unconnected-(U8-PA5-Pad3)") (class "Default")
      (node (ref "U8") (pin "3") (pinfunction "PA5_3") (pintype "unspecified"))
    )
    (net (code "80") (name "unconnected-(U8-PA7-Pad5)") (class "Default")
      (node (ref "U8") (pin "5") (pinfunction "PA7_5") (pintype "unspecified"))
    )
    (net (code "81") (name "unconnected-(U8-TOSC1{slash}PB3-Pad6)") (class "Default")
      (node (ref "U8") (pin "6") (pinfunction "TOSC1/PB3_6") (pintype "unspecified"))
    )
    (net (code "82") (name "unconnected-(U9-PA2-Pad12)") (class "Default")
      (node (ref "U9") (pin "12") (pinfunction "PA2_12") (pintype "unspecified"))
    )
    (net (code "83") (name "unconnected-(U9-PA5-Pad3)") (class "Default")
      (node (ref "U9") (pin "3") (pinfunction "PA5_3") (pintype "unspecified"))
    )
    (net (code "84") (name "unconnected-(U9-PA7-Pad5)") (class "Default")
      (node (ref "U9") (pin "5") (pinfunction "PA7_5") (pintype "unspecified"))
    )
    (net (code "85") (name "unconnected-(U9-TOSC1{slash}PB3-Pad6)") (class "Default")
      (node (ref "U9") (pin "6") (pinfunction "TOSC1/PB3_6") (pintype "unspecified"))
    )
    (net (code "86") (name "unconnected-(U10-PA2-Pad12)") (class "Default")
      (node (ref "U10") (pin "12") (pinfunction "PA2_12") (pintype "unspecified"))
    )
    (net (code "87") (name "unconnected-(U10-PA5-Pad3)") (class "Default")
      (node (ref "U10") (pin "3") (pinfunction "PA5_3") (pintype "unspecified"))
    )
    (net (code "88") (name "unconnected-(U10-PA7-Pad5)") (class "Default")
      (node (ref "U10") (pin "5") (pinfunction "PA7_5") (pintype "unspecified"))
    )
    (net (code "89") (name "unconnected-(U10-TOSC1{slash}PB3-Pad6)") (class "Default")
      (node (ref "U10") (pin "6") (pinfunction "TOSC1/PB3_6") (pintype "unspecified"))
    )
    (net (code "90") (name "unconnected-(U11-PA2-Pad12)") (class "Default")
      (node (ref "U11") (pin "12") (pinfunction "PA2_12") (pintype "unspecified"))
    )
    (net (code "91") (name "unconnected-(U11-PA5-Pad3)") (class "Default")
      (node (ref "U11") (pin "3") (pinfunction "PA5_3") (pintype "unspecified"))
    )
    (net (code "92") (name "unconnected-(U11-PA7-Pad5)") (class "Default")
      (node (ref "U11") (pin "5") (pinfunction "PA7_5") (pintype "unspecified"))
    )
    (net (code "93") (name "unconnected-(U11-TOSC1{slash}PB3-Pad6)") (class "Default")
      (node (ref "U11") (pin "6") (pinfunction "TOSC1/PB3_6") (pintype "unspecified"))
    )
  )
)
